# 5_spi_memory.net
KiCad netlist of a schematic drawn in Altium Designer
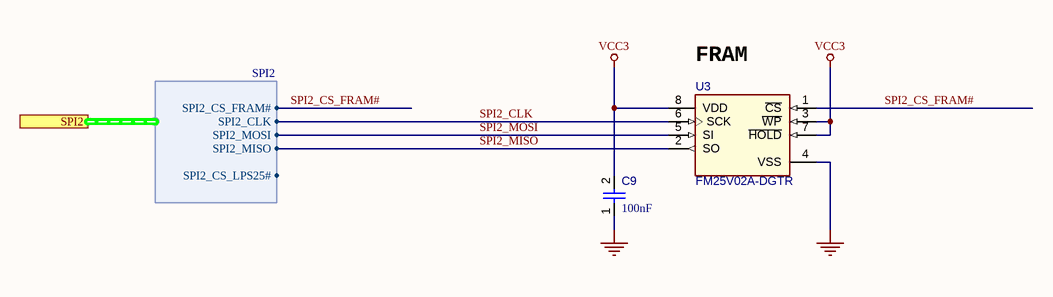
[diagram p0:  5_spi_memory.SchDoc]

(export (version "E")
  (design (tool "Eeschema 10.0.6"))
  (components
    (comp (ref "C9")
      (value "100nF")
      (footprint "CAPC0402(1005)60_L")
      (description "Chip Capacitor, 100nF +/-20%, 10V, 0402, Thickness 0.6 mm")
      (fields (field (name "TOLERANCE") "20%") (field (name "Comment") "Capacitor 100nF +/-20% 10V 0402"))
      (libsource (lib "MHH -  Altium Advanced Course A365 01") (part "CAP-NP-2"))
    )
    (comp (ref "U3")
      (value "FM25V02A-DGTR")
      (footprint "SON95P400X75_HS-9N")
      (description "REEL / F-RAM Memory Serial")
      (libsource (lib "Altium Designer Advanced Course 08") (part "CMP-019-00000-4"))
    )
  )
  (nets
    (net (code "2") (name "/SPI2_CLK") (class "Default")
      (node (ref "U3") (pin "6") (pinfunction "SCK_6") (pintype "input"))
    )
    (net (code "3") (name "/SPI2_CS_FRAM#") (class "Default")
      (node (ref "U3") (pin "1") (pinfunction "~{CS}_1") (pintype "input"))
    )
    (net (code "4") (name "/SPI2_MISO") (class "Default")
      (node (ref "U3") (pin "2") (pinfunction "SO_2") (pintype "output"))
    )
    (net (code "5") (name "/SPI2_MOSI") (class "Default")
      (node (ref "U3") (pin "5") (pinfunction "SI_5") (pintype "input"))
    )
    (net (code "7") (name "GND") (class "Default")
      (node (ref "C9") (pin "1") (pinfunction "1_1") (pintype "passive"))
      (node (ref "U3") (pin "4") (pinfunction "VSS_4") (pintype "power_in"))
    )
    (net (code "8") (name "VCC3") (class "Default")
      (node (ref "C9") (pin "2") (pinfunction "2_2") (pintype "passive"))
      (node (ref "U3") (pin "3") (pinfunction "~{WP}_3") (pintype "input"))
      (node (ref "U3") (pin "7") (pinfunction "~{HOLD}_7") (pintype "input"))
      (node (ref "U3") (pin "8") (pinfunction "VDD_8") (pintype "power_in"))
    )
  )
)
